# powersupply_grid8_0.net
KiCad netlist of a schematic drawn in Altium Designer
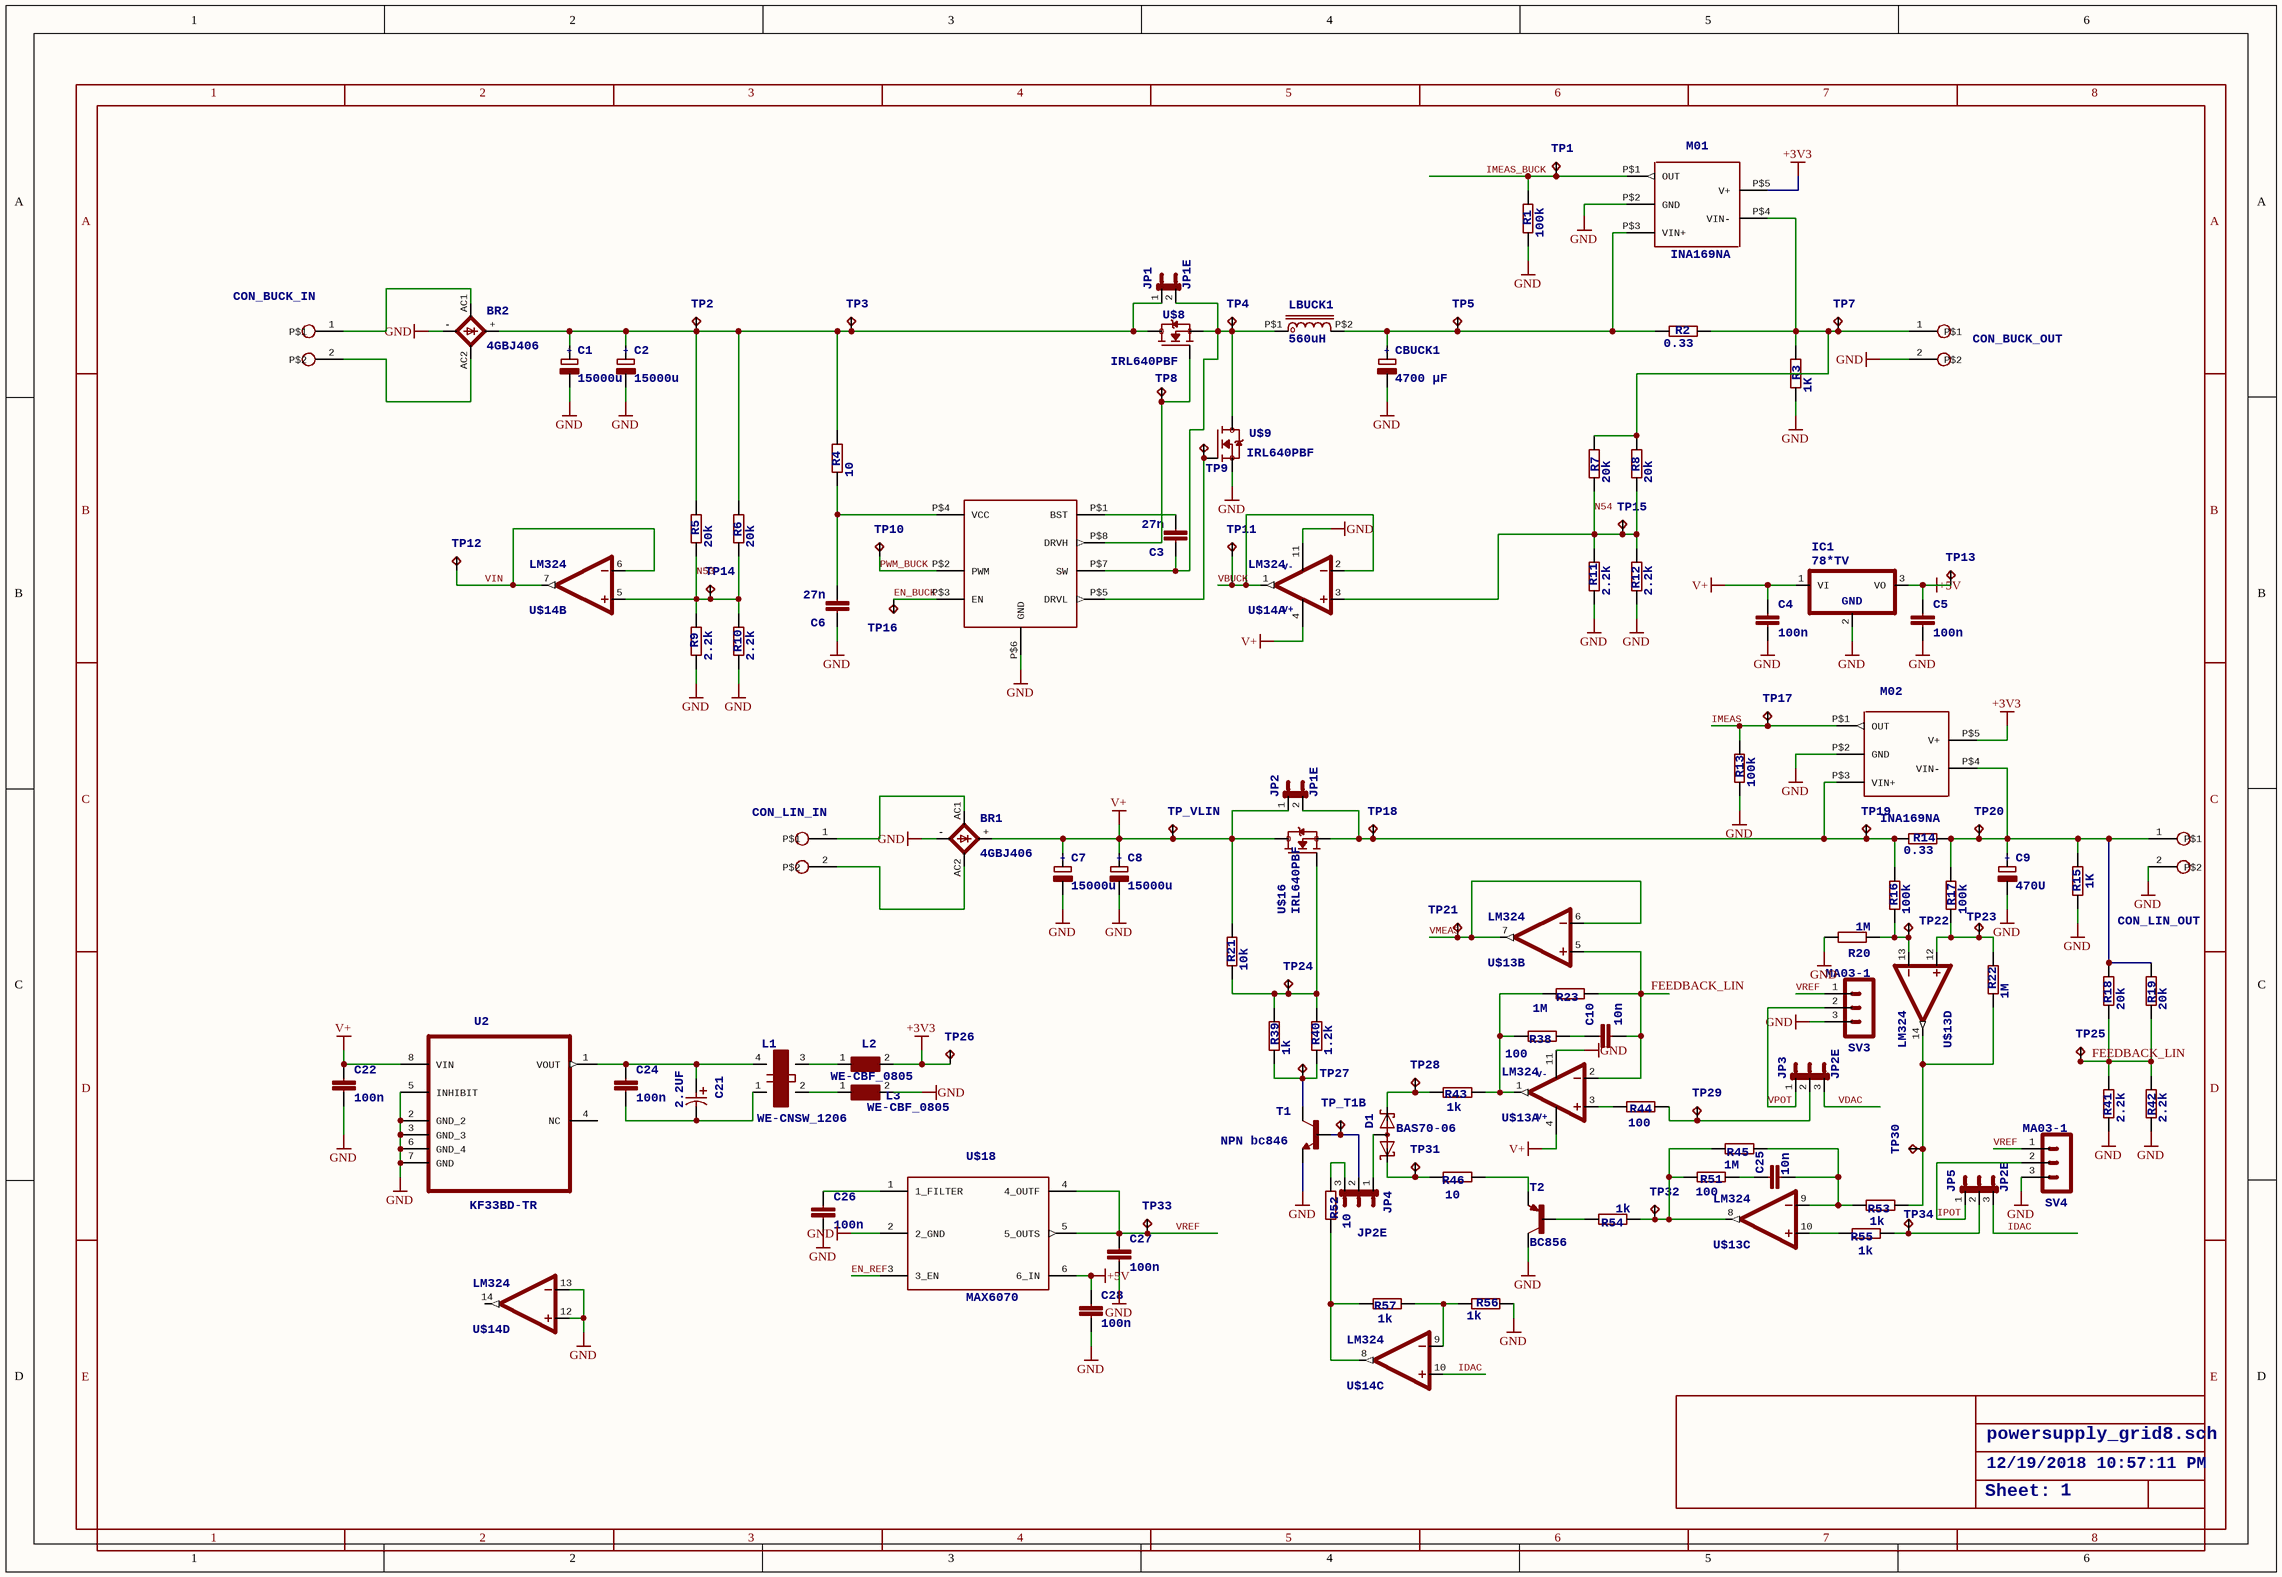
[diagram p0: powersupply_grid8_0.SchDoc]

(export (version "E")
  (design (tool "Eeschema 10.0.6"))
  (components
    (comp (ref "BR1") (value "4GBJ406") (footprint "FB100") (libsource (lib "4GBJ406F") (part "4GBJ406")))
    (comp (ref "BR2") (value "4GBJ406") (footprint "FB100") (libsource (lib "4GBJ406F") (part "4GBJ406")))
    (comp (ref "C1")
      (value "15000u")
      (footprint "EB30D")
      (description "<B>POLARIZED CAPACITOR</B>, European symbol")
      (fields (field (name "+") "+"))
      (libsource (lib "rcl") (part "CPOL-EUE10-30"))
    )
    (comp (ref "C2")
      (value "15000u")
      (footprint "EB30D")
      (description "<B>POLARIZED CAPACITOR</B>, European symbol")
      (fields (field (name "+") "+"))
      (libsource (lib "rcl") (part "CPOL-EUE10-30"))
    )
    (comp (ref "C3")
      (value "27n")
      (footprint "C0805")
      (description "<B>CAPACITOR</B>, European symbol")
      (libsource (lib "") (part "C-EUC0805_1"))
    )
    (comp (ref "C4")
      (value "100n")
      (footprint "C0402")
      (description "<B>CAPACITOR</B>, European symbol")
      (libsource (lib "rcl") (part "C-EUC0402"))
    )
    (comp (ref "C5")
      (value "100n")
      (footprint "C0402")
      (description "<B>CAPACITOR</B>, European symbol")
      (libsource (lib "rcl") (part "C-EUC0402"))
    )
    (comp (ref "C6")
      (value "27n")
      (footprint "C0805")
      (description "<B>CAPACITOR</B>, European symbol")
      (libsource (lib "") (part "C-EUC0805_1"))
    )
    (comp (ref "C7")
      (value "15000u")
      (footprint "EB30D")
      (description "<B>POLARIZED CAPACITOR</B>, European symbol")
      (fields (field (name "+") "+"))
      (libsource (lib "rcl") (part "CPOL-EUE10-30"))
    )
    (comp (ref "C8")
      (value "15000u")
      (footprint "EB30D")
      (description "<B>POLARIZED CAPACITOR</B>, European symbol")
      (fields (field (name "+") "+"))
      (libsource (lib "rcl") (part "CPOL-EUE10-30"))
    )
    (comp (ref "C9")
      (value "470U")
      (footprint "E5-13")
      (description "<B>POLARIZED CAPACITOR</B>, European symbol")
      (fields (field (name "+") "+"))
      (libsource (lib "rcl") (part "CPOL-EUE5-13"))
    )
    (comp (ref "C10")
      (value "10n")
      (footprint "C0805")
      (description "<B>CAPACITOR</B>, European symbol")
      (libsource (lib "rcl") (part "C-EUC0805"))
    )
    (comp (ref "C21")
      (value "2.2UF")
      (footprint "CAPAE430X610N")
      (description "Aluminum Electrolytic Capacitors,Surface Mount Type")
      (fields (field (name "MPN") "EEE-HC1HR47R") (field (name "TOLERANCE") "±20 %"))
      (libsource (lib "Panasonic-EEEFT_EEEH") (part "EEE--CASE-B"))
    )
    (comp (ref "C22")
      (value "100n")
      (footprint "C0603")
      (description "<B>CAPACITOR</B>, European symbol")
      (libsource (lib "rcl") (part "C-EUC0603"))
    )
    (comp (ref "C24")
      (value "100n")
      (footprint "C0603")
      (description "<B>CAPACITOR</B>, European symbol")
      (libsource (lib "rcl") (part "C-EUC0603"))
    )
    (comp (ref "C25")
      (value "10n")
      (footprint "C0805")
      (description "<B>CAPACITOR</B>, European symbol")
      (libsource (lib "rcl") (part "C-EUC0805"))
    )
    (comp (ref "C26")
      (value "100n")
      (footprint "C0402")
      (description "<B>CAPACITOR</B>, European symbol")
      (libsource (lib "rcl") (part "C-EUC0402"))
    )
    (comp (ref "C27")
      (value "100n")
      (footprint "C0402")
      (description "<B>CAPACITOR</B>, European symbol")
      (libsource (lib "rcl") (part "C-EUC0402"))
    )
    (comp (ref "C28")
      (value "100n")
      (footprint "C0402")
      (description "<B>CAPACITOR</B>, European symbol")
      (libsource (lib "rcl") (part "C-EUC0402"))
    )
    (comp (ref "CBUCK1")
      (value "4700 µF")
      (footprint "E7,5-18")
      (fields (field (name "+") "+"))
      (libsource (lib "B41888C7478M000") (part "B41888C7478M000"))
    )
    (comp (ref "CON_BUCK_IN")
      (value "POWERCON")
      (footprint "MKS1852-6-0-202")
      (libsource (lib "powercon") (part "POWERCON"))
    )
    (comp (ref "CON_BUCK_OUT")
      (value "POWERCON")
      (footprint "MKS1852-6-0-202")
      (libsource (lib "powercon") (part "POWERCON"))
    )
    (comp (ref "CON_LIN_IN")
      (value "POWERCON")
      (footprint "MKS1852-6-0-202")
      (libsource (lib "powercon") (part "POWERCON"))
    )
    (comp (ref "CON_LIN_OUT")
      (value "POWERCON")
      (footprint "MKS1852-6-0-202")
      (libsource (lib "powercon") (part "POWERCON"))
    )
    (comp (ref "D1")
      (value "BAS70-06")
      (footprint "SOT23")
      (description "<b>Silicon Schottky Diodes</b><p>\nGeneral-purpose diode for high-speed switching")
      (libsource (lib "diode") (part "BAS70-06"))
    )
    (comp (ref "IC1")
      (value "78*TV")
      (footprint "TO220V")
      (fields (field (name "GND") "GND"))
      (libsource (lib "linear") (part "78*TV"))
    )
    (comp (ref "JP1")
      (value "JP1E")
      (footprint "JP1")
      (description "<b>JUMPER</b>")
      (libsource (lib "jumper") (part "JP1E"))
    )
    (comp (ref "JP2")
      (value "JP1E")
      (footprint "JP1")
      (description "<b>JUMPER</b>")
      (libsource (lib "jumper") (part "JP1E"))
    )
    (comp (ref "JP3")
      (value "JP2E")
      (footprint "JP2")
      (description "<b>JUMPER</b>")
      (libsource (lib "jumper") (part "JP2E"))
    )
    (comp (ref "JP4")
      (value "JP2E")
      (footprint "JP2")
      (description "<b>JUMPER</b>")
      (libsource (lib "jumper") (part "JP2E"))
    )
    (comp (ref "JP5")
      (value "JP2E")
      (footprint "JP2")
      (description "<b>JUMPER</b>")
      (libsource (lib "jumper") (part "JP2E"))
    )
    (comp (ref "L1")
      (value "WE-CNSW_1206")
      (footprint "WE-CNSW_1206")
      (fields (field (name "MPN") "744232601"))
      (libsource (lib "WE-CNSW") (part "WE-CNSW_1206"))
    )
    (comp (ref "L2")
      (value "WE-CBF_0805")
      (footprint "0805")
      (fields (field (name "MPN") "742792097"))
      (libsource (lib "WE-CBF") (part "WE-CBF_0805"))
    )
    (comp (ref "L3")
      (value "WE-CBF_0805")
      (footprint "0805")
      (fields (field (name "MPN") "742792097"))
      (libsource (lib "WE-CBF") (part "WE-CBF_0805"))
    )
    (comp (ref "LBUCK1")
      (value "560uH")
      (footprint "PCV-2-564-08L")
      (libsource (lib "PCV-2-564-08L") (part "PCV-2-564-08L"))
    )
    (comp (ref "M01") (value "INA169NA") (footprint "SOT23") (libsource (lib "INA169NA") (part "INA169NA")))
    (comp (ref "M02") (value "INA169NA") (footprint "SOT23") (libsource (lib "INA169NA") (part "INA169NA")))
    (comp (ref "R1")
      (value "100k")
      (footprint "R0805")
      (description "<B>RESISTOR</B>, European symbol")
      (libsource (lib "rcl") (part "R-EU_R0805"))
    )
    (comp (ref "R2")
      (value "0.33")
      (footprint "R2010")
      (description "<B>RESISTOR</B>, European symbol")
      (libsource (lib "rcl") (part "R-EU_R2010"))
    )
    (comp (ref "R3")
      (value "1K")
      (footprint "R2512")
      (description "<B>RESISTOR</B>, European symbol")
      (libsource (lib "rcl") (part "R-EU_R2512"))
    )
    (comp (ref "R4")
      (value "10")
      (footprint "R0805")
      (description "<B>RESISTOR</B>, European symbol")
      (libsource (lib "rcl") (part "R-EU_R0805"))
    )
    (comp (ref "R5")
      (value "20k")
      (footprint "R0805")
      (description "<B>RESISTOR</B>, European symbol")
      (libsource (lib "rcl") (part "R-EU_R0805"))
    )
    (comp (ref "R6")
      (value "20k")
      (footprint "R0805")
      (description "<B>RESISTOR</B>, European symbol")
      (libsource (lib "rcl") (part "R-EU_R0805"))
    )
    (comp (ref "R7")
      (value "20k")
      (footprint "R0805")
      (description "<B>RESISTOR</B>, European symbol")
      (libsource (lib "rcl") (part "R-EU_R0805"))
    )
    (comp (ref "R8")
      (value "20k")
      (footprint "R0805")
      (description "<B>RESISTOR</B>, European symbol")
      (libsource (lib "rcl") (part "R-EU_R0805"))
    )
    (comp (ref "R9")
      (value "2.2k")
      (footprint "R0805")
      (description "<B>RESISTOR</B>, European symbol")
      (libsource (lib "rcl") (part "R-EU_R0805"))
    )
    (comp (ref "R10")
      (value "2.2k")
      (footprint "R0805")
      (description "<B>RESISTOR</B>, European symbol")
      (libsource (lib "rcl") (part "R-EU_R0805"))
    )
    (comp (ref "R11")
      (value "2.2k")
      (footprint "R0805")
      (description "<B>RESISTOR</B>, European symbol")
      (libsource (lib "rcl") (part "R-EU_R0805"))
    )
    (comp (ref "R12")
      (value "2.2k")
      (footprint "R0805")
      (description "<B>RESISTOR</B>, European symbol")
      (libsource (lib "rcl") (part "R-EU_R0805"))
    )
    (comp (ref "R13")
      (value "100k")
      (footprint "R0805")
      (description "<B>RESISTOR</B>, European symbol")
      (libsource (lib "rcl") (part "R-EU_R0805"))
    )
    (comp (ref "R14")
      (value "0.33")
      (footprint "R2010")
      (description "<B>RESISTOR</B>, European symbol")
      (libsource (lib "rcl") (part "R-EU_R2010"))
    )
    (comp (ref "R15")
      (value "1K")
      (footprint "R2512")
      (description "<B>RESISTOR</B>, European symbol")
      (libsource (lib "rcl") (part "R-EU_R2512"))
    )
    (comp (ref "R16")
      (value "100k")
      (footprint "R0805")
      (description "<B>RESISTOR</B>, European symbol")
      (libsource (lib "rcl") (part "R-EU_R0805"))
    )
    (comp (ref "R17")
      (value "100k")
      (footprint "R0805")
      (description "<B>RESISTOR</B>, European symbol")
      (libsource (lib "rcl") (part "R-EU_R0805"))
    )
    (comp (ref "R18")
      (value "20k")
      (footprint "R0805")
      (description "<B>RESISTOR</B>, European symbol")
      (libsource (lib "rcl") (part "R-EU_R0805"))
    )
    (comp (ref "R19")
      (value "20k")
      (footprint "R0805")
      (description "<B>RESISTOR</B>, European symbol")
      (libsource (lib "rcl") (part "R-EU_R0805"))
    )
    (comp (ref "R20")
      (value "1M")
      (footprint "R0805")
      (description "<B>RESISTOR</B>, European symbol")
      (libsource (lib "rcl") (part "R-EU_R0805"))
    )
    (comp (ref "R21")
      (value "10k")
      (footprint "R0805")
      (description "<B>RESISTOR</B>, European symbol")
      (libsource (lib "rcl") (part "R-EU_R0805"))
    )
    (comp (ref "R22")
      (value "1M")
      (footprint "R0805")
      (description "<B>RESISTOR</B>, European symbol")
      (libsource (lib "rcl") (part "R-EU_R0805"))
    )
    (comp (ref "R23")
      (value "1M")
      (footprint "R0805")
      (description "<B>RESISTOR</B>, European symbol")
      (libsource (lib "rcl") (part "R-EU_R0805"))
    )
    (comp (ref "R38")
      (value "100")
      (footprint "R0805")
      (description "<B>RESISTOR</B>, European symbol")
      (libsource (lib "rcl") (part "R-EU_R0805"))
    )
    (comp (ref "R39")
      (value "1k")
      (footprint "R0805")
      (description "<B>RESISTOR</B>, European symbol")
      (libsource (lib "rcl") (part "R-EU_R0805"))
    )
    (comp (ref "R40")
      (value "1.2k")
      (footprint "R0805")
      (description "<B>RESISTOR</B>, European symbol")
      (libsource (lib "rcl") (part "R-EU_R0805"))
    )
    (comp (ref "R41")
      (value "2.2k")
      (footprint "R0805")
      (description "<B>RESISTOR</B>, European symbol")
      (libsource (lib "rcl") (part "R-EU_R0805"))
    )
    (comp (ref "R42")
      (value "2.2k")
      (footprint "R0805")
      (description "<B>RESISTOR</B>, European symbol")
      (libsource (lib "rcl") (part "R-EU_R0805"))
    )
    (comp (ref "R43")
      (value "1k")
      (footprint "R0805")
      (description "<B>RESISTOR</B>, European symbol")
      (libsource (lib "rcl") (part "R-EU_R0805"))
    )
    (comp (ref "R44")
      (value "100")
      (footprint "R0805")
      (description "<B>RESISTOR</B>, European symbol")
      (libsource (lib "rcl") (part "R-EU_R0805"))
    )
    (comp (ref "R45")
      (value "1M")
      (footprint "R0805")
      (description "<B>RESISTOR</B>, European symbol")
      (libsource (lib "rcl") (part "R-EU_R0805"))
    )
    (comp (ref "R46")
      (value "10")
      (footprint "R0805")
      (description "<B>RESISTOR</B>, European symbol")
      (libsource (lib "rcl") (part "R-EU_R0805"))
    )
    (comp (ref "R51")
      (value "100")
      (footprint "R0805")
      (description "<B>RESISTOR</B>, European symbol")
      (libsource (lib "rcl") (part "R-EU_R0805"))
    )
    (comp (ref "R52")
      (value "10")
      (footprint "R0805")
      (description "<B>RESISTOR</B>, European symbol")
      (libsource (lib "rcl") (part "R-EU_R0805"))
    )
    (comp (ref "R53")
      (value "1k")
      (footprint "R0805")
      (description "<B>RESISTOR</B>, European symbol")
      (libsource (lib "rcl") (part "R-EU_R0805"))
    )
    (comp (ref "R54")
      (value "1k")
      (footprint "R0805")
      (description "<B>RESISTOR</B>, European symbol")
      (libsource (lib "rcl") (part "R-EU_R0805"))
    )
    (comp (ref "R55")
      (value "1k")
      (footprint "R0805")
      (description "<B>RESISTOR</B>, European symbol")
      (libsource (lib "rcl") (part "R-EU_R0805"))
    )
    (comp (ref "R56")
      (value "1k")
      (footprint "R0805")
      (description "<B>RESISTOR</B>, European symbol")
      (libsource (lib "rcl") (part "R-EU_R0805"))
    )
    (comp (ref "R57")
      (value "1k")
      (footprint "R0805")
      (description "<B>RESISTOR</B>, European symbol")
      (libsource (lib "rcl") (part "R-EU_R0805"))
    )
    (comp (ref "SV3")
      (value "MA03-1")
      (footprint "MA03-1")
      (description "<b>PIN HEADER</b>")
      (libsource (lib "con-lstb") (part "MA03-1"))
    )
    (comp (ref "SV4")
      (value "MA03-1")
      (footprint "MA03-1")
      (description "<b>PIN HEADER</b>")
      (libsource (lib "con-lstb") (part "MA03-1"))
    )
    (comp (ref "T1")
      (value "NPN bc846")
      (footprint "SOT23-BEC")
      (libsource (lib "transistor") (part "*-NPN-SOT23-BEC"))
    )
    (comp (ref "T2")
      (value "BC856")
      (footprint "SOT23-BEC")
      (description "PNP Transistror")
      (libsource (lib "transistor") (part "*-PNP-SOT23-BEC"))
    )
    (comp (ref "TP1")
      (value "TPB2,54")
      (footprint "B2,54")
      (description "<b>Test pad</b>")
      (libsource (lib "testpad") (part "TPB2,54"))
    )
    (comp (ref "TP2")
      (value "TPB2,54")
      (footprint "B2,54")
      (description "<b>Test pad</b>")
      (libsource (lib "testpad") (part "TPB2,54"))
    )
    (comp (ref "TP3")
      (value "TPB2,54")
      (footprint "B2,54")
      (description "<b>Test pad</b>")
      (libsource (lib "testpad") (part "TPB2,54"))
    )
    (comp (ref "TP4")
      (value "TPB2,54")
      (footprint "B2,54")
      (description "<b>Test pad</b>")
      (libsource (lib "testpad") (part "TPB2,54"))
    )
    (comp (ref "TP5")
      (value "TPB2,54")
      (footprint "B2,54")
      (description "<b>Test pad</b>")
      (libsource (lib "testpad") (part "TPB2,54"))
    )
    (comp (ref "TP7")
      (value "TPB2,54")
      (footprint "B2,54")
      (description "<b>Test pad</b>")
      (libsource (lib "testpad") (part "TPB2,54"))
    )
    (comp (ref "TP8")
      (value "TPB2,54")
      (footprint "B2,54")
      (description "<b>Test pad</b>")
      (libsource (lib "testpad") (part "TPB2,54"))
    )
    (comp (ref "TP9")
      (value "TPB2,54")
      (footprint "B2,54")
      (description "<b>Test pad</b>")
      (libsource (lib "testpad") (part "TPB2,54"))
    )
    (comp (ref "TP10")
      (value "TPB2,54")
      (footprint "B2,54")
      (description "<b>Test pad</b>")
      (libsource (lib "testpad") (part "TPB2,54"))
    )
    (comp (ref "TP11")
      (value "TPB2,54")
      (footprint "B2,54")
      (description "<b>Test pad</b>")
      (libsource (lib "testpad") (part "TPB2,54"))
    )
    (comp (ref "TP12")
      (value "TPB2,54")
      (footprint "B2,54")
      (description "<b>Test pad</b>")
      (libsource (lib "testpad") (part "TPB2,54"))
    )
    (comp (ref "TP13")
      (value "TPB2,54")
      (footprint "B2,54")
      (description "<b>Test pad</b>")
      (libsource (lib "testpad") (part "TPB2,54"))
    )
    (comp (ref "TP14")
      (value "TPB2,54")
      (footprint "B2,54")
      (description "<b>Test pad</b>")
      (libsource (lib "testpad") (part "TPB2,54"))
    )
    (comp (ref "TP15")
      (value "TPB2,54")
      (footprint "B2,54")
      (description "<b>Test pad</b>")
      (libsource (lib "testpad") (part "TPB2,54"))
    )
    (comp (ref "TP16")
      (value "TPB2,54")
      (footprint "B2,54")
      (description "<b>Test pad</b>")
      (libsource (lib "testpad") (part "TPB2,54"))
    )
    (comp (ref "TP17")
      (value "TPB2,54")
      (footprint "B2,54")
      (description "<b>Test pad</b>")
      (libsource (lib "testpad") (part "TPB2,54"))
    )
    (comp (ref "TP18")
      (value "TPB2,54")
      (footprint "B2,54")
      (description "<b>Test pad</b>")
      (libsource (lib "testpad") (part "TPB2,54"))
    )
    (comp (ref "TP19")
      (value "TPB2,54")
      (footprint "B2,54")
      (description "<b>Test pad</b>")
      (libsource (lib "testpad") (part "TPB2,54"))
    )
    (comp (ref "TP20")
      (value "TPB2,54")
      (footprint "B2,54")
      (description "<b>Test pad</b>")
      (libsource (lib "testpad") (part "TPB2,54"))
    )
    (comp (ref "TP21")
      (value "TPB2,54")
      (footprint "B2,54")
      (description "<b>Test pad</b>")
      (libsource (lib "testpad") (part "TPB2,54"))
    )
    (comp (ref "TP22")
      (value "TPB2,54")
      (footprint "B2,54")
      (description "<b>Test pad</b>")
      (libsource (lib "testpad") (part "TPB2,54"))
    )
    (comp (ref "TP23")
      (value "TPB2,54")
      (footprint "B2,54")
      (description "<b>Test pad</b>")
      (libsource (lib "testpad") (part "TPB2,54"))
    )
    (comp (ref "TP24")
      (value "TPB2,54")
      (footprint "B2,54")
      (description "<b>Test pad</b>")
      (libsource (lib "testpad") (part "TPB2,54"))
    )
    (comp (ref "TP25")
      (value "TPB2,54")
      (footprint "B2,54")
      (description "<b>Test pad</b>")
      (libsource (lib "testpad") (part "TPB2,54"))
    )
    (comp (ref "TP26")
      (value "TPB2,54")
      (footprint "B2,54")
      (description "<b>Test pad</b>")
      (libsource (lib "testpad") (part "TPB2,54"))
    )
    (comp (ref "TP27")
      (value "TPB2,54")
      (footprint "B2,54")
      (description "<b>Test pad</b>")
      (libsource (lib "testpad") (part "TPB2,54"))
    )
    (comp (ref "TP28")
      (value "TPB2,54")
      (footprint "B2,54")
      (description "<b>Test pad</b>")
      (libsource (lib "testpad") (part "TPB2,54"))
    )
    (comp (ref "TP29")
      (value "TPB2,54")
      (footprint "B2,54")
      (description "<b>Test pad</b>")
      (libsource (lib "testpad") (part "TPB2,54"))
    )
    (comp (ref "TP30")
      (value "TPB2,54")
      (footprint "B2,54")
      (description "<b>Test pad</b>")
      (libsource (lib "testpad") (part "TPB2,54"))
    )
    (comp (ref "TP31")
      (value "TPB2,54")
      (footprint "B2,54")
      (description "<b>Test pad</b>")
      (libsource (lib "testpad") (part "TPB2,54"))
    )
    (comp (ref "TP32")
      (value "TPB2,54")
      (footprint "B2,54")
      (description "<b>Test pad</b>")
      (libsource (lib "testpad") (part "TPB2,54"))
    )
    (comp (ref "TP33")
      (value "TPB2,54")
      (footprint "B2,54")
      (description "<b>Test pad</b>")
      (libsource (lib "testpad") (part "TPB2,54"))
    )
    (comp (ref "TP34")
      (value "TPB2,54")
      (footprint "B2,54")
      (description "<b>Test pad</b>")
      (libsource (lib "testpad") (part "TPB2,54"))
    )
    (comp (ref "TP_T1B")
      (value "TPB2,54")
      (footprint "B2,54")
      (description "<b>Test pad</b>")
      (libsource (lib "testpad") (part "TPB2,54"))
    )
    (comp (ref "TP_VLIN")
      (value "TPB2,54")
      (footprint "B2,54")
      (description "<b>Test pad</b>")
      (libsource (lib "testpad") (part "TPB2,54"))
    )
    (comp (ref "U$8")
      (value "IRL640PBF")
      (footprint "TO-220AB")
      (libsource (lib "TO-220AB") (part "IRL640PBF"))
    )
    (comp (ref "U$9")
      (value "IRL640PBF")
      (footprint "TO-220AB")
      (libsource (lib "TO-220AB") (part "IRL640PBF"))
    )
    (comp (ref "U$11") (value "NCP5901B") (footprint "SOIC-8") (libsource (lib "NCP5901B") (part "NCP5901B")))
    (comp (ref "U$13")
      (value "LM324")
      (footprint "SO14")
      (fields (field (name "V+") "V+") (field (name "V-") "V-"))
      (libsource (lib "lm324") (part "LM324"))
    )
    (comp (ref "U$14")
      (value "LM324")
      (footprint "SO14")
      (fields (field (name "V+") "V+") (field (name "V-") "V-"))
      (libsource (lib "lm324") (part "LM324"))
    )
    (comp (ref "U$16")
      (value "IRL640PBF")
      (footprint "TO-220AB")
      (libsource (lib "TO-220AB") (part "IRL640PBF"))
    )
    (comp (ref "U$18") (value "MAX6070") (footprint "SOT23-6") (libsource (lib "max6070") (part "MAX6070")))
    (comp (ref "U2")
      (value "KF33BD-TR")
      (footprint "SOIC127P600X175-8N")
      (description "LDO, 0.4VDO, 0.5A, 3.3V, 2%, 8SOIC")
      (libsource (lib "KF33BD-TR") (part "KF33BD-TR"))
    )
  )
  (nets
    (net (code "1") (name "+3V3") (class "Default")
      (node (ref "L2") (pin "2") (pinfunction "2_2") (pintype "passive"))
      (node (ref "M01") (pin "P$5") (pinfunction "V+_P$5") (pintype "power_in"))
      (node (ref "M02") (pin "P$5") (pinfunction "V+_P$5") (pintype "power_in"))
      (node (ref "TP26") (pin "TP") (pinfunction "TP_TP") (pintype "passive"))
    )
    (net (code "2") (name "+5V") (class "Default")
      (node (ref "C28") (pin "1") (pinfunction "1_1") (pintype "passive"))
      (node (ref "C5") (pin "1") (pinfunction "1_1") (pintype "passive"))
      (node (ref "IC1") (pin "3") (pinfunction "VO_3") (pintype "passive"))
      (node (ref "TP13") (pin "TP") (pinfunction "TP_TP") (pintype "passive"))
      (node (ref "U$18") (pin "6") (pinfunction "6_IN_6") (pintype "passive"))
    )
    (net (code "3") (name "/EN_BUCK") (class "Default")
      (node (ref "TP16") (pin "TP") (pinfunction "TP_TP") (pintype "passive"))
      (node (ref "U$11") (pin "P$3") (pinfunction "EN_P$3") (pintype "passive"))
    )
    (net (code "4") (name "/EN_REF") (class "Default")
      (node (ref "U$18") (pin "3") (pinfunction "3_EN_3") (pintype "passive"))
    )
    (net (code "5") (name "/FEEDBACK_LIN") (class "Default")
      (node (ref "C10") (pin "2") (pinfunction "2_2") (pintype "passive"))
      (node (ref "R18") (pin "1") (pinfunction "1_1") (pintype "passive"))
      (node (ref "R19") (pin "1") (pinfunction "1_1") (pintype "passive"))
      (node (ref "R23") (pin "1") (pinfunction "1_1") (pintype "passive"))
      (node (ref "R41") (pin "2") (pinfunction "2_2") (pintype "passive"))
      (node (ref "R42") (pin "2") (pinfunction "2_2") (pintype "passive"))
      (node (ref "TP25") (pin "TP") (pinfunction "TP_TP") (pintype "passive"))
      (node (ref "U$13") (pin "2") (pinfunction "-IN_2") (pintype "passive"))
      (node (ref "U$13") (pin "5") (pinfunction "+IN_5") (pintype "passive"))
    )
    (net (code "6") (name "/IDAC") (class "Default")
      (node (ref "JP5") (pin "3") (pinfunction "3_3") (pintype "passive"))
      (node (ref "U$14") (pin "10") (pinfunction "+IN_10") (pintype "passive"))
    )
    (net (code "7") (name "/IMEAS") (class "Default")
      (node (ref "M02") (pin "P$1") (pinfunction "OUT_P$1") (pintype "output"))
      (node (ref "R13") (pin "2") (pinfunction "2_2") (pintype "passive"))
      (node (ref "TP17") (pin "TP") (pinfunction "TP_TP") (pintype "passive"))
    )
    (net (code "8") (name "/IMEAS_BUCK") (class "Default")
      (node (ref "M01") (pin "P$1") (pinfunction "OUT_P$1") (pintype "output"))
      (node (ref "R1") (pin "2") (pinfunction "2_2") (pintype "passive"))
      (node (ref "TP1") (pin "TP") (pinfunction "TP_TP") (pintype "passive"))
    )
    (net (code "9") (name "/IPOT") (class "Default")
      (node (ref "JP5") (pin "1") (pinfunction "1_1") (pintype "passive"))
      (node (ref "SV4") (pin "2") (pinfunction "2_2") (pintype "passive"))
    )
    (net (code "10") (name "/N53") (class "Default")
      (node (ref "R10") (pin "2") (pinfunction "2_2") (pintype "passive"))
      (node (ref "R5") (pin "1") (pinfunction "1_1") (pintype "passive"))
      (node (ref "R6") (pin "1") (pinfunction "1_1") (pintype "passive"))
      (node (ref "R9") (pin "2") (pinfunction "2_2") (pintype "passive"))
      (node (ref "TP14") (pin "TP") (pinfunction "TP_TP") (pintype "passive"))
      (node (ref "U$14") (pin "5") (pinfunction "+IN_5") (pintype "passive"))
    )
    (net (code "11") (name "/N54") (class "Default")
      (node (ref "R11") (pin "2") (pinfunction "2_2") (pintype "passive"))
      (node (ref "R12") (pin "2") (pinfunction "2_2") (pintype "passive"))
      (node (ref "R7") (pin "1") (pinfunction "1_1") (pintype "passive"))
      (node (ref "R8") (pin "1") (pinfunction "1_1") (pintype "passive"))
      (node (ref "TP15") (pin "TP") (pinfunction "TP_TP") (pintype "passive"))
      (node (ref "U$14") (pin "3") (pinfunction "+IN_3") (pintype "passive"))
    )
    (net (code "12") (name "/PWM_BUCK") (class "Default")
      (node (ref "TP10") (pin "TP") (pinfunction "TP_TP") (pintype "passive"))
      (node (ref "U$11") (pin "P$2") (pinfunction "PWM_P$2") (pintype "passive"))
    )
    (net (code "13") (name "/VBUCK") (class "Default")
      (node (ref "TP11") (pin "TP") (pinfunction "TP_TP") (pintype "passive"))
      (node (ref "U$14") (pin "1") (pinfunction "OUT_1") (pintype "output"))
      (node (ref "U$14") (pin "2") (pinfunction "-IN_2") (pintype "passive"))
    )
    (net (code "14") (name "/VDAC") (class "Default")
      (node (ref "JP3") (pin "3") (pinfunction "3_3") (pintype "passive"))
    )
    (net (code "15") (name "/VIN") (class "Default")
      (node (ref "TP12") (pin "TP") (pinfunction "TP_TP") (pintype "passive"))
      (node (ref "U$14") (pin "6") (pinfunction "-IN_6") (pintype "passive"))
      (node (ref "U$14") (pin "7") (pinfunction "OUT_7") (pintype "output"))
    )
    (net (code "16") (name "/VMEAS") (class "Default")
      (node (ref "TP21") (pin "TP") (pinfunction "TP_TP") (pintype "passive"))
      (node (ref "U$13") (pin "6") (pinfunction "-IN_6") (pintype "passive"))
      (node (ref "U$13") (pin "7") (pinfunction "OUT_7") (pintype "output"))
    )
    (net (code "17") (name "/VPOT") (class "Default")
      (node (ref "JP3") (pin "1") (pinfunction "1_1") (pintype "passive"))
      (node (ref "SV3") (pin "2") (pinfunction "2_2") (pintype "passive"))
    )
    (net (code "18") (name "/VREF") (class "Default")
      (node (ref "C27") (pin "1") (pinfunction "1_1") (pintype "passive"))
      (node (ref "SV3") (pin "1") (pinfunction "1_1") (pintype "passive"))
      (node (ref "SV4") (pin "1") (pinfunction "1_1") (pintype "passive"))
      (node (ref "TP33") (pin "TP") (pinfunction "TP_TP") (pintype "passive"))
      (node (ref "U$18") (pin "4") (pinfunction "4_OUTF_4") (pintype "passive"))
      (node (ref "U$18") (pin "5") (pinfunction "5_OUTS_5") (pintype "output"))
    )
    (net (code "19") (name "GND") (class "Default")
      (node (ref "BR1") (pin "-") (pinfunction "-_-") (pintype "passive"))
      (node (ref "BR2") (pin "-") (pinfunction "-_-") (pintype "passive"))
      (node (ref "C1") (pin "-") (pinfunction "-_-") (pintype "passive"))
      (node (ref "C2") (pin "-") (pinfunction "-_-") (pintype "passive"))
      (node (ref "C22") (pin "2") (pinfunction "2_2") (pintype "passive"))
      (node (ref "C26") (pin "2") (pinfunction "2_2") (pintype "passive"))
      (node (ref "C27") (pin "2") (pinfunction "2_2") (pintype "passive"))
      (node (ref "C28") (pin "2") (pinfunction "2_2") (pintype "passive"))
      (node (ref "C4") (pin "2") (pinfunction "2_2") (pintype "passive"))
      (node (ref "C5") (pin "2") (pinfunction "2_2") (pintype "passive"))
      (node (ref "C6") (pin "1") (pinfunction "1_1") (pintype "passive"))
      (node (ref "C7") (pin "-") (pinfunction "-_-") (pintype "passive"))
      (node (ref "C8") (pin "-") (pinfunction "-_-") (pintype "passive"))
      (node (ref "C9") (pin "-") (pinfunction "-_-") (pintype "passive"))
      (node (ref "CBUCK1") (pin "-") (pinfunction "-_-") (pintype "passive"))
      (node (ref "CON_BUCK_OUT") (pin "2") (pinfunction "P$2_2") (pintype "passive"))
      (node (ref "CON_LIN_OUT") (pin "2") (pinfunction "P$2_2") (pintype "passive"))
      (node (ref "IC1") (pin "2") (pinfunction "GND_2") (pintype "passive"))
      (node (ref "L3") (pin "2") (pinfunction "2_2") (pintype "passive"))
      (node (ref "M01") (pin "P$2") (pinfunction "GND_P$2") (pintype "power_in"))
      (node (ref "M02") (pin "P$2") (pinfunction "GND_P$2") (pintype "power_in"))
      (node (ref "R1") (pin "1") (pinfunction "1_1") (pintype "passive"))
      (node (ref "R10") (pin "1") (pinfunction "1_1") (pintype "passive"))
      (node (ref "R11") (pin "1") (pinfunction "1_1") (pintype "passive"))
      (node (ref "R12") (pin "1") (pinfunction "1_1") (pintype "passive"))
      (node (ref "R13") (pin "1") (pinfunction "1_1") (pintype "passive"))
      (node (ref "R15") (pin "1") (pinfunction "1_1") (pintype "passive"))
      (node (ref "R20") (pin "2") (pinfunction "2_2") (pintype "passive"))
      (node (ref "R3") (pin "1") (pinfunction "1_1") (pintype "passive"))
      (node (ref "R41") (pin "1") (pinfunction "1_1") (pintype "passive"))
      (node (ref "R42") (pin "1") (pinfunction "1_1") (pintype "passive"))
      (node (ref "R56") (pin "2") (pinfunction "2_2") (pintype "passive"))
      (node (ref "R9") (pin "1") (pinfunction "1_1") (pintype "passive"))
      (node (ref "SV3") (pin "3") (pinfunction "3_3") (pintype "passive"))
      (node (ref "SV4") (pin "3") (pinfunction "3_3") (pintype "passive"))
      (node (ref "T1") (pin "E") (pinfunction "E_E") (pintype "passive"))
      (node (ref "T2") (pin "C") (pinfunction "C_C") (pintype "passive"))
      (node (ref "U$11") (pin "P$6") (pinfunction "GND_P$6") (pintype "power_in"))
      (node (ref "U$13") (pin "11") (pinfunction "V-_11") (pintype "power_in"))
      (node (ref "U$14") (pin "11") (pinfunction "V-_11") (pintype "power_in"))
      (node (ref "U$14") (pin "12") (pinfunction "+IN_12") (pintype "passive"))
      (node (ref "U$14") (pin "13") (pinfunction "-IN_13") (pintype "passive"))
      (node (ref "U$18") (pin "2") (pinfunction "2_GND_2") (pintype "power_in"))
      (node (ref "U$9") (pin "P$3") (pinfunction "S_P$3") (pintype "passive"))
      (node (ref "U2") (pin "2") (pinfunction "GND_2_2") (pintype "passive"))
      (node (ref "U2") (pin "3") (pinfunction "GND_3_3") (pintype "passive"))
      (node (ref "U2") (pin "5") (pinfunction "INHIBIT_5") (pintype "passive"))
      (node (ref "U2") (pin "6") (pinfunction "GND_4_6") (pintype "passive"))
      (node (ref "U2") (pin "7") (pinfunction "GND_7") (pintype "passive"))
    )
    (net (code "20") (name "Net-(C10-Pad1)") (class "Default")
      (node (ref "C10") (pin "1") (pinfunction "1_1") (pintype "passive"))
      (node (ref "R38") (pin "1") (pinfunction "1_1") (pintype "passive"))
    )
    (net (code "21") (name "Net-(C21-Pad2)") (class "Default")
      (node (ref "C21") (pin "2") (pinfunction "2_2") (pintype "passive"))
      (node (ref "C24") (pin "2") (pinfunction "2_2") (pintype "passive"))
      (node (ref "L1") (pin "1") (pinfunction "1_1") (pintype "passive"))
    )
    (net (code "22") (name "Net-(C25-Pad1)") (class "Default")
      (node (ref "C25") (pin "1") (pinfunction "1_1") (pintype "passive"))
      (node (ref "R51") (pin "1") (pinfunction "1_1") (pintype "passive"))
    )
    (net (code "23") (name "Net-(CON_BUCK_IN-P$1)") (class "Default")
      (node (ref "BR2") (pin "AC1") (pinfunction "AC1_AC1") (pintype "passive"))
      (node (ref "CON_BUCK_IN") (pin "1") (pinfunction "P$1_1") (pintype "passive"))
    )
    (net (code "24") (name "Net-(CON_BUCK_IN-P$2)") (class "Default")
      (node (ref "BR2") (pin "AC2") (pinfunction "AC2_AC2") (pintype "passive"))
      (node (ref "CON_BUCK_IN") (pin "2") (pinfunction "P$2_2") (pintype "passive"))
    )
    (net (code "25") (name "Net-(CON_BUCK_OUT-P$1)") (class "Default")
      (node (ref "CON_BUCK_OUT") (pin "1") (pinfunction "P$1_1") (pintype "passive"))
      (node (ref "M01") (pin "P$4") (pinfunction "VIN-_P$4") (pintype "passive"))
      (node (ref "R2") (pin "2") (pinfunction "2_2") (pintype "passive"))
      (node (ref "R3") (pin "2") (pinfunction "2_2") (pintype "passive"))
      (node (ref "R7") (pin "2") (pinfunction "2_2") (pintype "passive"))
      (node (ref "R8") (pin "2") (pinfunction "2_2") (pintype "passive"))
      (node (ref "TP7") (pin "TP") (pinfunction "TP_TP") (pintype "passive"))
    )
    (net (code "26") (name "Net-(CON_LIN_IN-P$1)") (class "Default")
      (node (ref "BR1") (pin "AC1") (pinfunction "AC1_AC1") (pintype "passive"))
      (node (ref "CON_LIN_IN") (pin "1") (pinfunction "P$1_1") (pintype "passive"))
    )
    (net (code "27") (name "Net-(CON_LIN_IN-P$2)") (class "Default")
      (node (ref "BR1") (pin "AC2") (pinfunction "AC2_AC2") (pintype "passive"))
      (node (ref "CON_LIN_IN") (pin "2") (pinfunction "P$2_2") (pintype "passive"))
    )
    (net (code "28") (name "Net-(CON_LIN_OUT-P$1)") (class "Default")
      (node (ref "C9") (pin "+") (pinfunction "+_+") (pintype "passive"))
      (node (ref "CON_LIN_OUT") (pin "1") (pinfunction "P$1_1") (pintype "passive"))
      (node (ref "M02") (pin "P$4") (pinfunction "VIN-_P$4") (pintype "passive"))
      (node (ref "R14") (pin "2") (pinfunction "2_2") (pintype "passive"))
      (node (ref "R15") (pin "2") (pinfunction "2_2") (pintype "passive"))
      (node (ref "R17") (pin "2") (pinfunction "2_2") (pintype "passive"))
      (node (ref "R18") (pin "2") (pinfunction "2_2") (pintype "passive"))
      (node (ref "R19") (pin "2") (pinfunction "2_2") (pintype "passive"))
      (node (ref "TP20") (pin "TP") (pinfunction "TP_TP") (pintype "passive"))
    )
    (net (code "29") (name "Net-(D1-AA)") (class "Default")
      (node (ref "D1") (pin "3") (pinfunction "AA_3") (pintype "passive"))
      (node (ref "JP4") (pin "1") (pinfunction "1_1") (pintype "passive"))
    )
    (net (code "30") (name "Net-(D1-K1)") (class "Default")
      (node (ref "D1") (pin "1") (pinfunction "K1_1") (pintype "passive"))
      (node (ref "R46") (pin "2") (pinfunction "2_2") (pintype "passive"))
      (node (ref "TP31") (pin "TP") (pinfunction "TP_TP") (pintype "passive"))
    )
    (net (code "31") (name "Net-(D1-K2)") (class "Default")
      (node (ref "D1") (pin "2") (pinfunction "K2_2") (pintype "passive"))
      (node (ref "R43") (pin "2") (pinfunction "2_2") (pintype "passive"))
      (node (ref "TP28") (pin "TP") (pinfunction "TP_TP") (pintype "passive"))
    )
    (net (code "32") (name "Net-(JP3-Pad2)") (class "Default")
      (node (ref "JP3") (pin "2") (pinfunction "2_2") (pintype "passive"))
      (node (ref "R44") (pin "1") (pinfunction "1_1") (pintype "passive"))
      (node (ref "TP29") (pin "TP") (pinfunction "TP_TP") (pintype "passive"))
    )
    (net (code "33") (name "Net-(JP4-Pad2)") (class "Default")
      (node (ref "JP4") (pin "2") (pinfunction "2_2") (pintype "passive"))
      (node (ref "T1") (pin "B") (pinfunction "B_B") (pintype "passive"))
      (node (ref "TP_T1B") (pin "TP") (pinfunction "TP_TP") (pintype "passive"))
    )
    (net (code "34") (name "Net-(JP4-Pad3)") (class "Default")
      (node (ref "JP4") (pin "3") (pinfunction "3_3") (pintype "passive"))
      (node (ref "R52") (pin "1") (pinfunction "1_1") (pintype "passive"))
    )
    (net (code "35") (name "Net-(JP5-Pad2)") (class "Default")
      (node (ref "JP5") (pin "2") (pinfunction "2_2") (pintype "passive"))
      (node (ref "R55") (pin "1") (pinfunction "1_1") (pintype "passive"))
      (node (ref "TP34") (pin "TP") (pinfunction "TP_TP") (pintype "passive"))
    )
    (net (code "36") (name "Net-(L1-3)") (class "Default")
      (node (ref "C21") (pin "1") (pinfunction "1_1") (pintype "passive"))
      (node (ref "C24") (pin "1") (pinfunction "1_1") (pintype "passive"))
      (node (ref "L1") (pin "4") (pinfunction "3_4") (pintype "passive"))
      (node (ref "U2") (pin "1") (pinfunction "VOUT_1") (pintype "output"))
    )
    (net (code "37") (name "Net-(L1-4)") (class "Default")
      (node (ref "L1") (pin "3") (pinfunction "4_3") (pintype "passive"))
      (node (ref "L2") (pin "1") (pinfunction "1_1") (pintype "passive"))
    )
    (net (code "38") (name "Net-(L1-Pad2)") (class "Default")
      (node (ref "L1") (pin "2") (pinfunction "2_2") (pintype "passive"))
      (node (ref "L3") (pin "1") (pinfunction "1_1") (pintype "passive"))
    )
    (net (code "39") (name "Net-(LBUCK1-1)") (class "Default")
      (node (ref "C3") (pin "1") (pinfunction "1_1") (pintype "passive"))
      (node (ref "JP1") (pin "2") (pinfunction "2_2") (pintype "passive"))
      (node (ref "LBUCK1") (pin "P$1") (pinfunction "1_P$1") (pintype "passive"))
      (node (ref "TP4") (pin "TP") (pinfunction "TP_TP") (pintype "passive"))
      (node (ref "U$11") (pin "P$7") (pinfunction "SW_P$7") (pintype "passive"))
      (node (ref "U$8") (pin "P$3") (pinfunction "S_P$3") (pintype "passive"))
      (node (ref "U$9") (pin "P$2") (pinfunction "D_P$2") (pintype "passive"))
    )
    (net (code "40") (name "Net-(LBUCK1-4)") (class "Default")
      (node (ref "CBUCK1") (pin "+") (pinfunction "+_+") (pintype "passive"))
      (node (ref "LBUCK1") (pin "P$2") (pinfunction "4_P$2") (pintype "passive"))
      (node (ref "M01") (pin "P$3") (pinfunction "VIN+_P$3") (pintype "passive"))
      (node (ref "R2") (pin "1") (pinfunction "1_1") (pintype "passive"))
      (node (ref "TP5") (pin "TP") (pinfunction "TP_TP") (pintype "passive"))
    )
    (net (code "41") (name "Net-(M02-VIN+)") (class "Default")
      (node (ref "JP2") (pin "2") (pinfunction "2_2") (pintype "passive"))
      (node (ref "M02") (pin "P$3") (pinfunction "VIN+_P$3") (pintype "passive"))
      (node (ref "R14") (pin "1") (pinfunction "1_1") (pintype "passive"))
      (node (ref "R16") (pin "2") (pinfunction "2_2") (pintype "passive"))
      (node (ref "TP18") (pin "TP") (pinfunction "TP_TP") (pintype "passive"))
      (node (ref "TP19") (pin "TP") (pinfunction "TP_TP") (pintype "passive"))
      (node (ref "U$16") (pin "P$3") (pinfunction "S_P$3") (pintype "passive"))
    )
    (net (code "42") (name "Net-(R39-Pad1)") (class "Default")
      (node (ref "R39") (pin "1") (pinfunction "1_1") (pintype "passive"))
      (node (ref "R40") (pin "1") (pinfunction "1_1") (pintype "passive"))
      (node (ref "T1") (pin "C") (pinfunction "C_C") (pintype "passive"))
      (node (ref "TP27") (pin "TP") (pinfunction "TP_TP") (pintype "passive"))
    )
    (net (code "43") (name "Net-(R46-Pad1)") (class "Default")
      (node (ref "R46") (pin "1") (pinfunction "1_1") (pintype "passive"))
      (node (ref "T2") (pin "E") (pinfunction "E_E") (pintype "passive"))
    )
    (net (code "44") (name "Net-(R54-Pad2)") (class "Default")
      (node (ref "R54") (pin "2") (pinfunction "2_2") (pintype "passive"))
      (node (ref "T2") (pin "B") (pinfunction "B_B") (pintype "passive"))
    )
    (net (code "45") (name "Net-(U$8-D)") (class "Default")
      (node (ref "BR2") (pin "+") (pinfunction "+_+") (pintype "passive"))
      (node (ref "C1") (pin "+") (pinfunction "+_+") (pintype "passive"))
      (node (ref "C2") (pin "+") (pinfunction "+_+") (pintype "passive"))
      (node (ref "JP1") (pin "1") (pinfunction "1_1") (pintype "passive"))
      (node (ref "R4") (pin "2") (pinfunction "2_2") (pintype "passive"))
      (node (ref "R5") (pin "2") (pinfunction "2_2") (pintype "passive"))
      (node (ref "R6") (pin "2") (pinfunction "2_2") (pintype "passive"))
      (node (ref "TP2") (pin "TP") (pinfunction "TP_TP") (pintype "passive"))
      (node (ref "TP3") (pin "TP") (pinfunction "TP_TP") (pintype "passive"))
      (node (ref "U$8") (pin "P$2") (pinfunction "D_P$2") (pintype "passive"))
    )
    (net (code "46") (name "Net-(U$11-BST)") (class "Default")
      (node (ref "C3") (pin "2") (pinfunction "2_2") (pintype "passive"))
      (node (ref "U$11") (pin "P$1") (pinfunction "BST_P$1") (pintype "passive"))
    )
    (net (code "47") (name "Net-(U$11-DRVH)") (class "Default")
      (node (ref "TP8") (pin "TP") (pinfunction "TP_TP") (pintype "passive"))
      (node (ref "U$11") (pin "P$8") (pinfunction "DRVH_P$8") (pintype "output"))
      (node (ref "U$8") (pin "P$1") (pinfunction "G_P$1") (pintype "passive"))
    )
    (net (code "48") (name "Net-(U$11-DRVL)") (class "Default")
      (node (ref "TP9") (pin "TP") (pinfunction "TP_TP") (pintype "passive"))
      (node (ref "U$11") (pin "P$5") (pinfunction "DRVL_P$5") (pintype "output"))
      (node (ref "U$9") (pin "P$1") (pinfunction "G_P$1") (pintype "passive"))
    )
    (net (code "49") (name "Net-(U$11-VCC)") (class "Default")
      (node (ref "C6") (pin "2") (pinfunction "2_2") (pintype "passive"))
      (node (ref "R4") (pin "1") (pinfunction "1_1") (pintype "passive"))
      (node (ref "U$11") (pin "P$4") (pinfunction "VCC_P$4") (pintype "power_in"))
    )
    (net (code "50") (name "Net-(U$13A-+IN)") (class "Default")
      (node (ref "R44") (pin "2") (pinfunction "2_2") (pintype "passive"))
      (node (ref "U$13") (pin "3") (pinfunction "+IN_3") (pintype "passive"))
    )
    (net (code "51") (name "Net-(U$13A-OUT)") (class "Default")
      (node (ref "R23") (pin "2") (pinfunction "2_2") (pintype "passive"))
      (node (ref "R38") (pin "2") (pinfunction "2_2") (pintype "passive"))
      (node (ref "R43") (pin "1") (pinfunction "1_1") (pintype "passive"))
      (node (ref "U$13") (pin "1") (pinfunction "OUT_1") (pintype "output"))
    )
    (net (code "52") (name "Net-(U$13C-+IN)") (class "Default")
      (node (ref "R55") (pin "2") (pinfunction "2_2") (pintype "passive"))
      (node (ref "U$13") (pin "10") (pinfunction "+IN_10") (pintype "passive"))
    )
    (net (code "53") (name "Net-(U$13C--IN)") (class "Default")
      (node (ref "C25") (pin "2") (pinfunction "2_2") (pintype "passive"))
      (node (ref "R45") (pin "1") (pinfunction "1_1") (pintype "passive"))
      (node (ref "R53") (pin "2") (pinfunction "2_2") (pintype "passive"))
      (node (ref "U$13") (pin "9") (pinfunction "-IN_9") (pintype "passive"))
    )
    (net (code "54") (name "Net-(U$13C-OUT)") (class "Default")
      (node (ref "R45") (pin "2") (pinfunction "2_2") (pintype "passive"))
      (node (ref "R51") (pin "2") (pinfunction "2_2") (pintype "passive"))
      (node (ref "R54") (pin "1") (pinfunction "1_1") (pintype "passive"))
      (node (ref "TP32") (pin "TP") (pinfunction "TP_TP") (pintype "passive"))
      (node (ref "U$13") (pin "8") (pinfunction "OUT_8") (pintype "output"))
    )
    (net (code "55") (name "Net-(U$13D-+IN)") (class "Default")
      (node (ref "R17") (pin "1") (pinfunction "1_1") (pintype "passive"))
      (node (ref "R22") (pin "2") (pinfunction "2_2") (pintype "passive"))
      (node (ref "TP23") (pin "TP") (pinfunction "TP_TP") (pintype "passive"))
      (node (ref "U$13") (pin "12") (pinfunction "+IN_12") (pintype "passive"))
    )
    (net (code "56") (name "Net-(U$13D--IN)") (class "Default")
      (node (ref "R16") (pin "1") (pinfunction "1_1") (pintype "passive"))
      (node (ref "R20") (pin "1") (pinfunction "1_1") (pintype "passive"))
      (node (ref "TP22") (pin "TP") (pinfunction "TP_TP") (pintype "passive"))
      (node (ref "U$13") (pin "13") (pinfunction "-IN_13") (pintype "passive"))
    )
    (net (code "57") (name "Net-(U$13D-OUT)") (class "Default")
      (node (ref "R22") (pin "1") (pinfunction "1_1") (pintype "passive"))
      (node (ref "R53") (pin "1") (pinfunction "1_1") (pintype "passive"))
      (node (ref "TP30") (pin "TP") (pinfunction "TP_TP") (pintype "passive"))
      (node (ref "U$13") (pin "14") (pinfunction "OUT_14") (pintype "output"))
    )
    (net (code "58") (name "Net-(U$14C--IN)") (class "Default")
      (node (ref "R56") (pin "1") (pinfunction "1_1") (pintype "passive"))
      (node (ref "R57") (pin "1") (pinfunction "1_1") (pintype "passive"))
      (node (ref "U$14") (pin "9") (pinfunction "-IN_9") (pintype "passive"))
    )
    (net (code "59") (name "Net-(U$14C-OUT)") (class "Default")
      (node (ref "R52") (pin "2") (pinfunction "2_2") (pintype "passive"))
      (node (ref "R57") (pin "2") (pinfunction "2_2") (pintype "passive"))
      (node (ref "U$14") (pin "8") (pinfunction "OUT_8") (pintype "output"))
    )
    (net (code "60") (name "Net-(U$16-G)") (class "Default")
      (node (ref "R21") (pin "1") (pinfunction "1_1") (pintype "passive"))
      (node (ref "R39") (pin "2") (pinfunction "2_2") (pintype "passive"))
      (node (ref "R40") (pin "2") (pinfunction "2_2") (pintype "passive"))
      (node (ref "TP24") (pin "TP") (pinfunction "TP_TP") (pintype "passive"))
      (node (ref "U$16") (pin "P$1") (pinfunction "G_P$1") (pintype "passive"))
    )
    (net (code "61") (name "Net-(U$18-1_FILTER)") (class "Default")
      (node (ref "C26") (pin "1") (pinfunction "1_1") (pintype "passive"))
      (node (ref "U$18") (pin "1") (pinfunction "1_FILTER_1") (pintype "passive"))
    )
    (net (code "62") (name "V+") (class "Default")
      (node (ref "BR1") (pin "+") (pinfunction "+_+") (pintype "passive"))
      (node (ref "C22") (pin "1") (pinfunction "1_1") (pintype "passive"))
      (node (ref "C4") (pin "1") (pinfunction "1_1") (pintype "passive"))
      (node (ref "C7") (pin "+") (pinfunction "+_+") (pintype "passive"))
      (node (ref "C8") (pin "+") (pinfunction "+_+") (pintype "passive"))
      (node (ref "IC1") (pin "1") (pinfunction "VI_1") (pintype "passive"))
      (node (ref "JP2") (pin "1") (pinfunction "1_1") (pintype "passive"))
      (node (ref "R21") (pin "2") (pinfunction "2_2") (pintype "passive"))
      (node (ref "TP_VLIN") (pin "TP") (pinfunction "TP_TP") (pintype "passive"))
      (node (ref "U$13") (pin "4") (pinfunction "V+_4") (pintype "power_in"))
      (node (ref "U$14") (pin "4") (pinfunction "V+_4") (pintype "power_in"))
      (node (ref "U$16") (pin "P$2") (pinfunction "D_P$2") (pintype "passive"))
      (node (ref "U2") (pin "8") (pinfunction "VIN_8") (pintype "passive"))
    )
    (net (code "63") (name "unconnected-(U$14D-OUT-Pad14)") (class "Default")
      (node (ref "U$14") (pin "14") (pinfunction "OUT_14") (pintype "output"))
    )
    (net (code "64") (name "unconnected-(U2-NC-Pad4)") (class "Default")
      (node (ref "U2") (pin "4") (pinfunction "NC_4") (pintype "passive"))
    )
  )
)
